# Tracksoar_v1.net
KiCad netlist of a schematic drawn in EAGLE
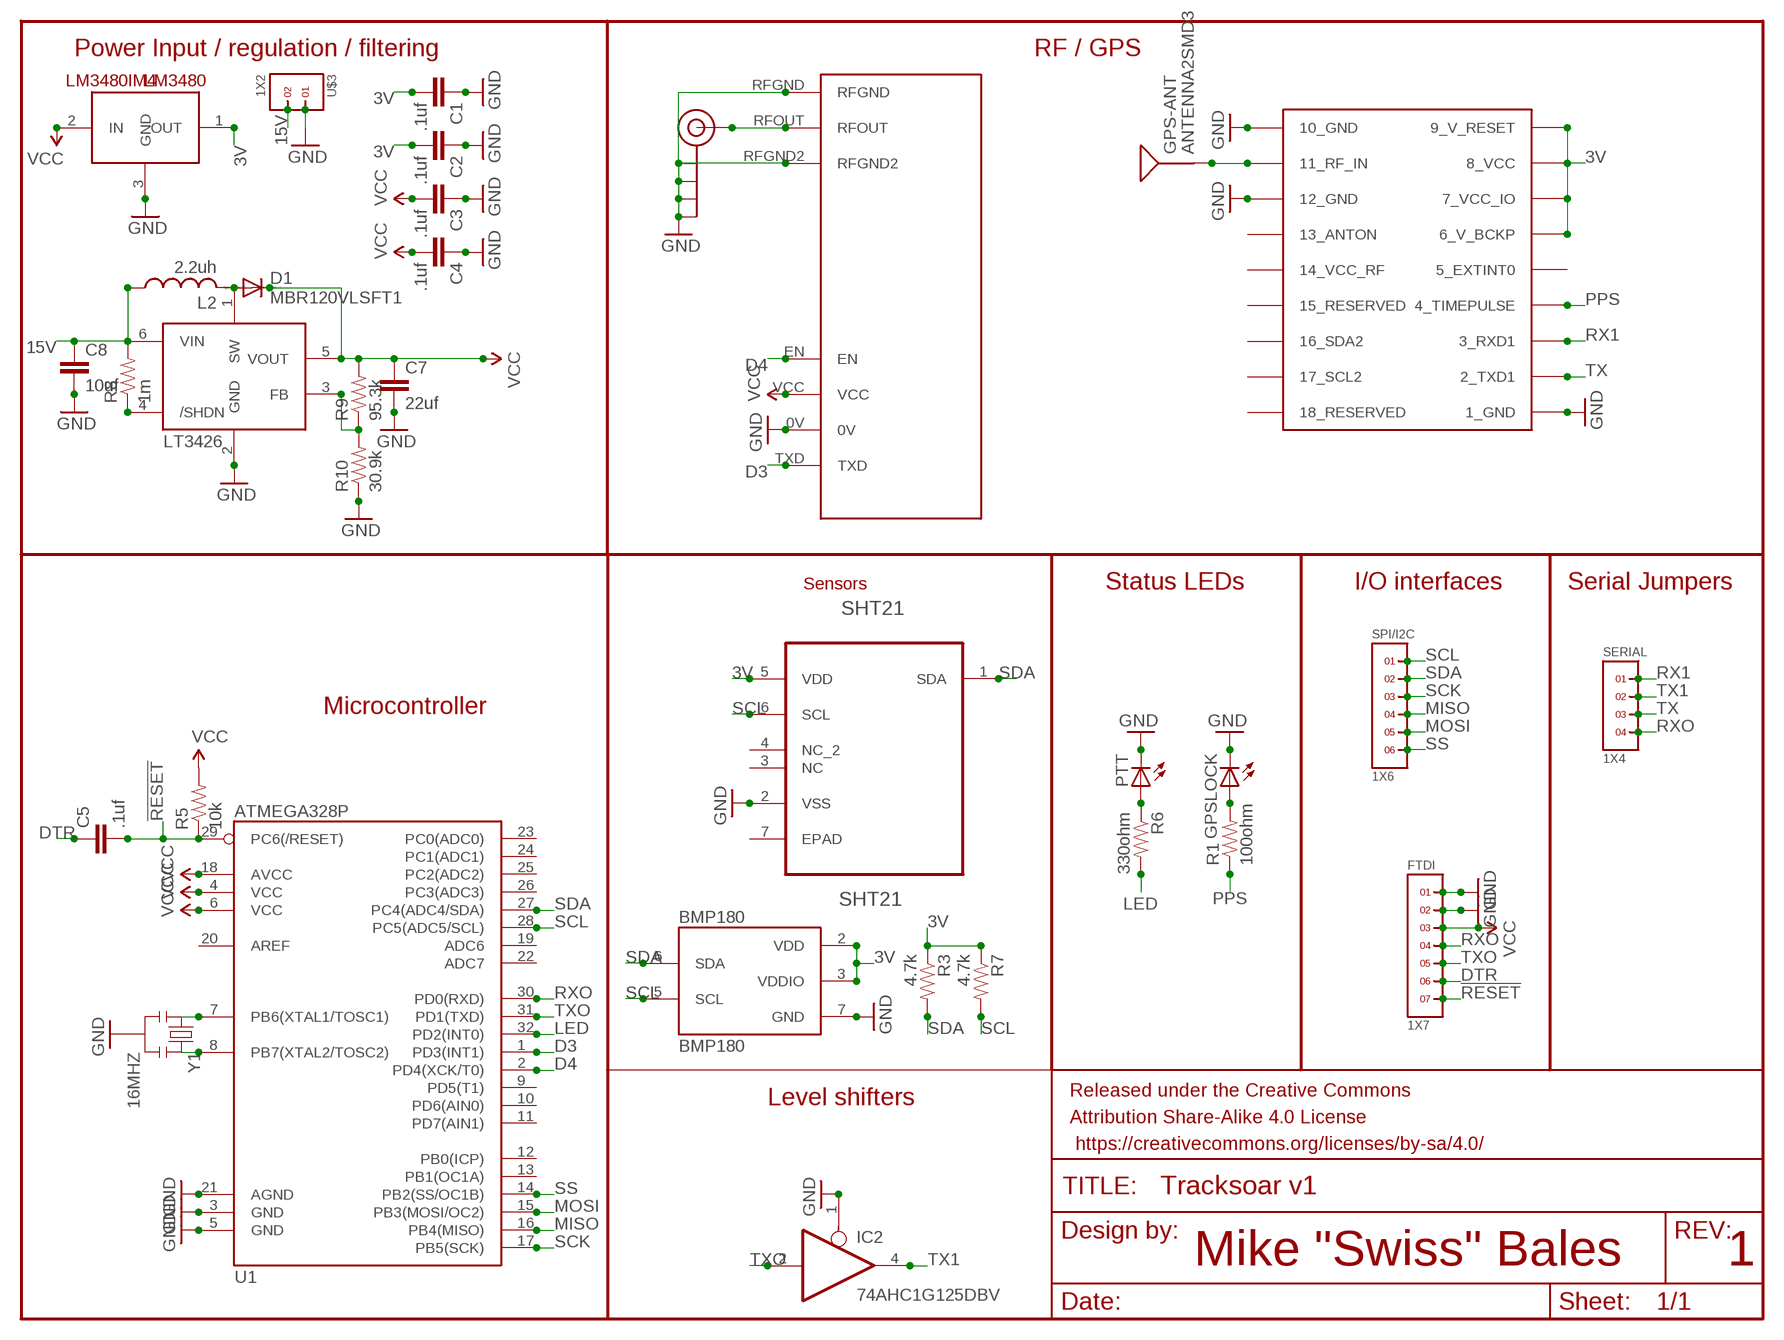
[diagram p0: schematic, sheet 1]

(export (version "E")
  (design (tool "Eeschema 10.0.6"))
  (components
    (comp (ref "BMP180")
      (value "BMP180")
      (footprint "eagle-import:BMP180")
      (libsource (lib "eagle-import") (part "BMP180"))
    )
    (comp (ref "C1")
      (value ".1uf")
      (footprint "eagle-import:0805")
      (libsource (lib "eagle-import") (part "CAP0805"))
    )
    (comp (ref "C2")
      (value ".1uf")
      (footprint "eagle-import:0805")
      (libsource (lib "eagle-import") (part "CAP0805"))
    )
    (comp (ref "C3")
      (value ".1uf")
      (footprint "eagle-import:0805")
      (libsource (lib "eagle-import") (part "CAP0805"))
    )
    (comp (ref "C4")
      (value ".1uf")
      (footprint "eagle-import:0805")
      (libsource (lib "eagle-import") (part "CAP0805"))
    )
    (comp (ref "C5")
      (value ".1uf")
      (footprint "eagle-import:0805")
      (libsource (lib "eagle-import") (part "CAP0805"))
    )
    (comp (ref "C7")
      (value "22uf")
      (footprint "eagle-import:0805")
      (libsource (lib "eagle-import") (part "CAP0805"))
    )
    (comp (ref "C8")
      (value "10uf")
      (footprint "eagle-import:0805")
      (libsource (lib "eagle-import") (part "CAP0805"))
    )
    (comp (ref "D1")
      (value "MBR120VLSFT1")
      (footprint "eagle-import:SOD123")
      (libsource (lib "eagle-import") (part "DIODE-SOD123"))
    )
    (comp (ref "FRAME1")
      (value "FRAME-LETTER")
      (footprint "eagle-import:CREATIVE_COMMONS")
      (libsource (lib "eagle-import") (part "FRAME-LETTER"))
    )
    (comp (ref "FTDI")
      (value "1X7")
      (footprint "eagle-import:1X7")
      (libsource (lib "eagle-import") (part "1X7"))
    )
    (comp (ref "GPS-ANT")
      (value "ANTENNA2SMD3")
      (footprint "eagle-import:ANTENNA-CHIP4")
      (libsource (lib "eagle-import") (part "ANTENNA2SMD3"))
    )
    (comp (ref "GPSLOCK")
      (value "LEDCHIP-LED0805")
      (footprint "eagle-import:CHIP-LED0805")
      (libsource (lib "eagle-import") (part "LEDCHIP-LED0805"))
    )
    (comp (ref "IC2")
      (value "74AHC1G125DBV")
      (footprint "eagle-import:SOT23-5")
      (libsource (lib "eagle-import") (part "741G125DBVAHC"))
    )
    (comp (ref "J$1")
      (value "SMA_EDGE")
      (footprint "eagle-import:SMA-EDGE")
      (libsource (lib "eagle-import") (part "SMA_EDGE"))
    )
    (comp (ref "L2")
      (value "2.2uh")
      (footprint "eagle-import:L1812")
      (libsource (lib "eagle-import") (part "L-USL1812"))
    )
    (comp (ref "LM3480")
      (value "LM3480IM4")
      (footprint "eagle-import:SOT23-3")
      (libsource (lib "eagle-import") (part "LM3480IM4"))
    )
    (comp (ref "LT3426")
      (value "LT3426")
      (footprint "eagle-import:SOT23-6")
      (libsource (lib "eagle-import") (part "LT3426"))
    )
    (comp (ref "PTT")
      (value "LEDCHIP-LED0805")
      (footprint "eagle-import:CHIP-LED0805")
      (libsource (lib "eagle-import") (part "LEDCHIP-LED0805"))
    )
    (comp (ref "R1")
      (value "100ohm")
      (footprint "eagle-import:0805")
      (libsource (lib "eagle-import") (part "RESISTOR0805-RES"))
    )
    (comp (ref "R3")
      (value "4.7k")
      (footprint "eagle-import:0805")
      (libsource (lib "eagle-import") (part "RESISTOR0805-RES"))
    )
    (comp (ref "R5")
      (value "10k")
      (footprint "eagle-import:0805")
      (libsource (lib "eagle-import") (part "RESISTOR0805-RES"))
    )
    (comp (ref "R6")
      (value "330ohm")
      (footprint "eagle-import:0805")
      (libsource (lib "eagle-import") (part "RESISTOR0805-RES"))
    )
    (comp (ref "R7")
      (value "4.7k")
      (footprint "eagle-import:0805")
      (libsource (lib "eagle-import") (part "RESISTOR0805-RES"))
    )
    (comp (ref "R8")
      (value "1m")
      (footprint "eagle-import:0805")
      (libsource (lib "eagle-import") (part "RESISTOR0805-RES"))
    )
    (comp (ref "R9")
      (value "95.3k")
      (footprint "eagle-import:0805")
      (libsource (lib "eagle-import") (part "RESISTOR0805-RES"))
    )
    (comp (ref "R10")
      (value "30.9k")
      (footprint "eagle-import:0805")
      (libsource (lib "eagle-import") (part "RESISTOR0805-RES"))
    )
    (comp (ref "SERIAL")
      (value "1X4")
      (footprint "eagle-import:1X4")
      (libsource (lib "eagle-import") (part "1X4"))
    )
    (comp (ref "SHT21")
      (value "SHT21")
      (footprint "eagle-import:DFN300X300X110-7N")
      (libsource (lib "eagle-import") (part "SHT21"))
    )
    (comp (ref "SPI/I2C")
      (value "1X6")
      (footprint "eagle-import:1X6")
      (libsource (lib "eagle-import") (part "1X6"))
    )
    (comp (ref "U$1")
      (value "UBLOX_MAX")
      (footprint "eagle-import:UBLOX_MAX")
      (libsource (lib "eagle-import") (part "UBLOX_MAX"))
    )
    (comp (ref "U$2")
      (value "RADIOMETRIX-HX1")
      (footprint "eagle-import:RADIOMETRIX-HX1")
      (libsource (lib "eagle-import") (part "RADIOMETRIX-HX1"))
    )
    (comp (ref "U$3")
      (value "1X2")
      (footprint "eagle-import:1X2")
      (libsource (lib "eagle-import") (part "1X2"))
    )
    (comp (ref "U1")
      (value "ATMEGA328P")
      (footprint "eagle-import:MLF32")
      (libsource (lib "eagle-import") (part "ATMEGA168MLF"))
    )
    (comp (ref "Y1")
      (value "16MHZ")
      (footprint "eagle-import:RESONATOR-SMD")
      (libsource (lib "eagle-import") (part "RESONATOR16MHZ"))
    )
  )
  (nets
    (net (code "1") (name "/3V") (class "Default")
      (node (ref "BMP180") (pin "2") (pinfunction "VDD_2") (pintype "power_in"))
      (node (ref "BMP180") (pin "3") (pinfunction "VDDIO_3") (pintype "power_in"))
      (node (ref "C1") (pin "2") (pinfunction "2_2") (pintype "passive"))
      (node (ref "C2") (pin "2") (pinfunction "2_2") (pintype "passive"))
      (node (ref "LM3480") (pin "1") (pinfunction "OUT_1") (pintype "bidirectional"))
      (node (ref "R3") (pin "1") (pinfunction "1_1") (pintype "passive"))
      (node (ref "R7") (pin "1") (pinfunction "1_1") (pintype "passive"))
      (node (ref "SHT21") (pin "5") (pinfunction "VDD_5") (pintype "power_in"))
      (node (ref "U$1") (pin "6_V_BCKP") (pinfunction "6_V_BCKP_6_V_BCKP") (pintype "bidirectional"))
      (node (ref "U$1") (pin "7_VCC_IO") (pinfunction "7_VCC_IO_7_VCC_IO") (pintype "power_in"))
      (node (ref "U$1") (pin "8_VCC") (pinfunction "8_VCC_8_VCC") (pintype "power_in"))
      (node (ref "U$1") (pin "9_V_RESET") (pinfunction "9_V_RESET_9_V_RESET") (pintype "power_in"))
    )
    (net (code "2") (name "/15V") (class "Default")
      (node (ref "C8") (pin "1") (pinfunction "1_1") (pintype "passive"))
      (node (ref "L2") (pin "1") (pinfunction "1_1") (pintype "passive"))
      (node (ref "LT3426") (pin "6") (pinfunction "VIN_6") (pintype "input"))
      (node (ref "R8") (pin "2") (pinfunction "2_2") (pintype "passive"))
      (node (ref "U$3") (pin "2") (pinfunction "2_2") (pintype "bidirectional"))
    )
    (net (code "3") (name "/D3") (class "Default")
      (node (ref "U$2") (pin "TXD") (pinfunction "TXD_TXD") (pintype "bidirectional"))
      (node (ref "U1") (pin "1") (pinfunction "PD3(INT1)_1") (pintype "bidirectional"))
    )
    (net (code "4") (name "/D4") (class "Default")
      (node (ref "U$2") (pin "EN") (pinfunction "EN_EN") (pintype "bidirectional"))
      (node (ref "U1") (pin "2") (pinfunction "PD4(XCK/T0)_2") (pintype "bidirectional"))
    )
    (net (code "5") (name "/DTR") (class "Default")
      (node (ref "C5") (pin "1") (pinfunction "1_1") (pintype "passive"))
      (node (ref "FTDI") (pin "6") (pinfunction "6_6") (pintype "bidirectional"))
    )
    (net (code "6") (name "/LED") (class "Default")
      (node (ref "R6") (pin "2") (pinfunction "2_2") (pintype "passive"))
      (node (ref "U1") (pin "32") (pinfunction "PD2(INT0)_32") (pintype "bidirectional"))
    )
    (net (code "7") (name "/MISO") (class "Default")
      (node (ref "SPI/I2C") (pin "4") (pinfunction "4_4") (pintype "bidirectional"))
      (node (ref "U1") (pin "16") (pinfunction "PB4(MISO)_16") (pintype "bidirectional"))
    )
    (net (code "8") (name "/MOSI") (class "Default")
      (node (ref "SPI/I2C") (pin "5") (pinfunction "5_5") (pintype "bidirectional"))
      (node (ref "U1") (pin "15") (pinfunction "PB3(MOSI/OC2)_15") (pintype "bidirectional"))
    )
    (net (code "9") (name "/PPS") (class "Default")
      (node (ref "R1") (pin "1") (pinfunction "1_1") (pintype "passive"))
      (node (ref "U$1") (pin "4_TIMEPULSE") (pinfunction "4_TIMEPULSE_4_TIMEPULSE") (pintype "bidirectional"))
    )
    (net (code "10") (name "/RX1") (class "Default")
      (node (ref "SERIAL") (pin "1") (pinfunction "1_1") (pintype "bidirectional"))
      (node (ref "U$1") (pin "3_RXD1") (pinfunction "3_RXD1_3_RXD1") (pintype "bidirectional"))
    )
    (net (code "11") (name "/RXO") (class "Default")
      (node (ref "FTDI") (pin "4") (pinfunction "4_4") (pintype "bidirectional"))
      (node (ref "SERIAL") (pin "4") (pinfunction "4_4") (pintype "bidirectional"))
      (node (ref "U1") (pin "30") (pinfunction "PD0(RXD)_30") (pintype "bidirectional"))
    )
    (net (code "12") (name "/SCK") (class "Default")
      (node (ref "SPI/I2C") (pin "3") (pinfunction "3_3") (pintype "bidirectional"))
      (node (ref "U1") (pin "17") (pinfunction "PB5(SCK)_17") (pintype "bidirectional"))
    )
    (net (code "13") (name "/SCL") (class "Default")
      (node (ref "BMP180") (pin "5") (pinfunction "SCL_5") (pintype "input"))
      (node (ref "R7") (pin "2") (pinfunction "2_2") (pintype "passive"))
      (node (ref "SHT21") (pin "6") (pinfunction "SCL_6") (pintype "input"))
      (node (ref "SPI/I2C") (pin "1") (pinfunction "1_1") (pintype "bidirectional"))
      (node (ref "U1") (pin "28") (pinfunction "PC5(ADC5/SCL)_28") (pintype "bidirectional"))
    )
    (net (code "14") (name "/SDA") (class "Default")
      (node (ref "BMP180") (pin "6") (pinfunction "SDA_6") (pintype "bidirectional"))
      (node (ref "R3") (pin "2") (pinfunction "2_2") (pintype "passive"))
      (node (ref "SHT21") (pin "1") (pinfunction "SDA_1") (pintype "bidirectional"))
      (node (ref "SPI/I2C") (pin "2") (pinfunction "2_2") (pintype "bidirectional"))
      (node (ref "U1") (pin "27") (pinfunction "PC4(ADC4/SDA)_27") (pintype "bidirectional"))
    )
    (net (code "15") (name "/SS") (class "Default")
      (node (ref "SPI/I2C") (pin "6") (pinfunction "6_6") (pintype "bidirectional"))
      (node (ref "U1") (pin "14") (pinfunction "PB2(SS/OC1B)_14") (pintype "bidirectional"))
    )
    (net (code "16") (name "/TX") (class "Default")
      (node (ref "SERIAL") (pin "3") (pinfunction "3_3") (pintype "bidirectional"))
      (node (ref "U$1") (pin "2_TXD1") (pinfunction "2_TXD1_2_TXD1") (pintype "bidirectional"))
    )
    (net (code "17") (name "/TX1") (class "Default")
      (node (ref "IC2") (pin "4") (pinfunction "O_4") (pintype "tri_state"))
      (node (ref "SERIAL") (pin "2") (pinfunction "2_2") (pintype "bidirectional"))
    )
    (net (code "18") (name "/TXO") (class "Default")
      (node (ref "FTDI") (pin "5") (pinfunction "5_5") (pintype "bidirectional"))
      (node (ref "IC2") (pin "2") (pinfunction "I_2") (pintype "input"))
      (node (ref "U1") (pin "31") (pinfunction "PD1(TXD)_31") (pintype "bidirectional"))
    )
    (net (code "19") (name "/~{RESET}") (class "Default")
      (node (ref "C5") (pin "2") (pinfunction "2_2") (pintype "passive"))
      (node (ref "FTDI") (pin "7") (pinfunction "7_7") (pintype "bidirectional"))
      (node (ref "R5") (pin "1") (pinfunction "1_1") (pintype "passive"))
      (node (ref "U1") (pin "29") (pinfunction "PC6(/RESET)_29") (pintype "bidirectional"))
    )
    (net (code "20") (name "GND") (class "Default")
      (node (ref "BMP180") (pin "7") (pinfunction "GND_7") (pintype "power_in"))
      (node (ref "C1") (pin "1") (pinfunction "1_1") (pintype "passive"))
      (node (ref "C2") (pin "1") (pinfunction "1_1") (pintype "passive"))
      (node (ref "C3") (pin "1") (pinfunction "1_1") (pintype "passive"))
      (node (ref "C4") (pin "1") (pinfunction "1_1") (pintype "passive"))
      (node (ref "C7") (pin "2") (pinfunction "2_2") (pintype "passive"))
      (node (ref "C8") (pin "2") (pinfunction "2_2") (pintype "passive"))
      (node (ref "FTDI") (pin "1") (pinfunction "1_1") (pintype "bidirectional"))
      (node (ref "FTDI") (pin "2") (pinfunction "2_2") (pintype "bidirectional"))
      (node (ref "GPSLOCK") (pin "C") (pinfunction "C_C") (pintype "passive"))
      (node (ref "IC2") (pin "1") (pinfunction "OE_1") (pintype "input"))
      (node (ref "J$1") (pin "GND@0") (pinfunction "GND_GND@0") (pintype "bidirectional"))
      (node (ref "J$1") (pin "GND@1") (pinfunction "GND_GND@1") (pintype "bidirectional"))
      (node (ref "J$1") (pin "GND@2") (pinfunction "GND_GND@2") (pintype "bidirectional"))
      (node (ref "J$1") (pin "GND@3") (pinfunction "GND_GND@3") (pintype "bidirectional"))
      (node (ref "LM3480") (pin "3") (pinfunction "GND_3") (pintype "bidirectional"))
      (node (ref "LT3426") (pin "2") (pinfunction "GND_2") (pintype "power_in"))
      (node (ref "PTT") (pin "C") (pinfunction "C_C") (pintype "passive"))
      (node (ref "R10") (pin "1") (pinfunction "1_1") (pintype "passive"))
      (node (ref "SHT21") (pin "2") (pinfunction "VSS_2") (pintype "power_in"))
      (node (ref "U$1") (pin "10_GND") (pinfunction "10_GND_10_GND") (pintype "power_in"))
      (node (ref "U$1") (pin "12_GND") (pinfunction "12_GND_12_GND") (pintype "power_in"))
      (node (ref "U$1") (pin "1_GND") (pinfunction "1_GND_1_GND") (pintype "power_in"))
      (node (ref "U$2") (pin "0V") (pinfunction "0V_0V") (pintype "bidirectional"))
      (node (ref "U$2") (pin "RFGND") (pinfunction "RFGND_RFGND") (pintype "bidirectional"))
      (node (ref "U$2") (pin "RFGND2") (pinfunction "RFGND2_RFGND2") (pintype "bidirectional"))
      (node (ref "U$3") (pin "1") (pinfunction "1_1") (pintype "bidirectional"))
      (node (ref "U1") (pin "21") (pinfunction "AGND_21") (pintype "bidirectional"))
      (node (ref "U1") (pin "3") (pinfunction "GND_3") (pintype "bidirectional"))
      (node (ref "U1") (pin "5") (pinfunction "GND_5") (pintype "bidirectional"))
      (node (ref "Y1") (pin "2") (pinfunction "2_2") (pintype "passive"))
    )
    (net (code "21") (name "Net-(GPS-ANT-SIGNAL)") (class "Default")
      (node (ref "GPS-ANT") (pin "SIG") (pinfunction "SIGNAL_SIG") (pintype "bidirectional"))
      (node (ref "U$1") (pin "11_RF_IN") (pinfunction "11_RF_IN_11_RF_IN") (pintype "bidirectional"))
    )
    (net (code "22") (name "Net-(GPSLOCK-PadA)") (class "Default")
      (node (ref "GPSLOCK") (pin "A") (pinfunction "A_A") (pintype "passive"))
      (node (ref "R1") (pin "2") (pinfunction "2_2") (pintype "passive"))
    )
    (net (code "23") (name "Net-(J$1-SIGNAL)") (class "Default")
      (node (ref "J$1") (pin "SIG") (pinfunction "SIGNAL_SIG") (pintype "bidirectional"))
      (node (ref "U$2") (pin "RFOUT") (pinfunction "RFOUT_RFOUT") (pintype "bidirectional"))
    )
    (net (code "24") (name "Net-(LT3426-FB)") (class "Default")
      (node (ref "LT3426") (pin "3") (pinfunction "FB_3") (pintype "input"))
      (node (ref "R10") (pin "2") (pinfunction "2_2") (pintype "passive"))
      (node (ref "R9") (pin "1") (pinfunction "1_1") (pintype "passive"))
    )
    (net (code "25") (name "Net-(LT3426-SW)") (class "Default")
      (node (ref "D1") (pin "A") (pinfunction "A_A") (pintype "passive"))
      (node (ref "L2") (pin "2") (pinfunction "2_2") (pintype "passive"))
      (node (ref "LT3426") (pin "1") (pinfunction "SW_1") (pintype "output"))
    )
    (net (code "26") (name "Net-(LT3426-{slash}SHDN)") (class "Default")
      (node (ref "LT3426") (pin "4") (pinfunction "/SHDN_4") (pintype "input"))
      (node (ref "R8") (pin "1") (pinfunction "1_1") (pintype "passive"))
    )
    (net (code "27") (name "Net-(PTT-PadA)") (class "Default")
      (node (ref "PTT") (pin "A") (pinfunction "A_A") (pintype "passive"))
      (node (ref "R6") (pin "1") (pinfunction "1_1") (pintype "passive"))
    )
    (net (code "28") (name "Net-(U1-PB6(XTAL1{slash}TOSC1))") (class "Default")
      (node (ref "U1") (pin "7") (pinfunction "PB6(XTAL1/TOSC1)_7") (pintype "bidirectional"))
      (node (ref "Y1") (pin "1") (pinfunction "1_1") (pintype "passive"))
    )
    (net (code "29") (name "Net-(U1-PB7(XTAL2{slash}TOSC2))") (class "Default")
      (node (ref "U1") (pin "8") (pinfunction "PB7(XTAL2/TOSC2)_8") (pintype "bidirectional"))
      (node (ref "Y1") (pin "3") (pinfunction "3_3") (pintype "passive"))
    )
    (net (code "30") (name "VCC") (class "Default")
      (node (ref "C3") (pin "2") (pinfunction "2_2") (pintype "passive"))
      (node (ref "C4") (pin "2") (pinfunction "2_2") (pintype "passive"))
      (node (ref "C7") (pin "1") (pinfunction "1_1") (pintype "passive"))
      (node (ref "D1") (pin "C") (pinfunction "C_C") (pintype "passive"))
      (node (ref "FTDI") (pin "3") (pinfunction "3_3") (pintype "bidirectional"))
      (node (ref "LM3480") (pin "2") (pinfunction "IN_2") (pintype "bidirectional"))
      (node (ref "LT3426") (pin "5") (pinfunction "VOUT_5") (pintype "output"))
      (node (ref "R5") (pin "2") (pinfunction "2_2") (pintype "passive"))
      (node (ref "R9") (pin "2") (pinfunction "2_2") (pintype "passive"))
      (node (ref "U$2") (pin "VCC") (pinfunction "VCC_VCC") (pintype "bidirectional"))
      (node (ref "U1") (pin "18") (pinfunction "AVCC_18") (pintype "bidirectional"))
      (node (ref "U1") (pin "4") (pinfunction "VCC_4") (pintype "bidirectional"))
      (node (ref "U1") (pin "6") (pinfunction "VCC_6") (pintype "bidirectional"))
    )
    (net (code "31") (name "unconnected-(SHT21-EPAD-Pad7)") (class "Default")
      (node (ref "SHT21") (pin "7") (pinfunction "EPAD_7") (pintype "passive"))
    )
    (net (code "32") (name "unconnected-(SHT21-NC-Pad3)") (class "Default")
      (node (ref "SHT21") (pin "3") (pinfunction "NC_3") (pintype "no_connect"))
    )
    (net (code "33") (name "unconnected-(SHT21-NC_2-Pad4)") (class "Default")
      (node (ref "SHT21") (pin "4") (pinfunction "NC_2_4") (pintype "no_connect"))
    )
    (net (code "34") (name "unconnected-(U$1-Pad5_EXTINT0)") (class "Default")
      (node (ref "U$1") (pin "5_EXTINT0") (pinfunction "5_EXTINT0_5_EXTINT0") (pintype "bidirectional"))
    )
    (net (code "35") (name "unconnected-(U$1-Pad13_ANTON)") (class "Default")
      (node (ref "U$1") (pin "13_ANTON") (pinfunction "13_ANTON_13_ANTON") (pintype "bidirectional"))
    )
    (net (code "36") (name "unconnected-(U$1-Pad14_VCC_RF)") (class "Default")
      (node (ref "U$1") (pin "14_VCC_RF") (pinfunction "14_VCC_RF_14_VCC_RF") (pintype "bidirectional"))
    )
    (net (code "37") (name "unconnected-(U$1-Pad15_RESERVED)") (class "Default")
      (node (ref "U$1") (pin "15_RESERVED") (pinfunction "15_RESERVED_15_RESERVED") (pintype "bidirectional"))
    )
    (net (code "38") (name "unconnected-(U$1-Pad16_SDA2)") (class "Default")
      (node (ref "U$1") (pin "16_SDA2") (pinfunction "16_SDA2_16_SDA2") (pintype "bidirectional"))
    )
    (net (code "39") (name "unconnected-(U$1-Pad17_SCL2)") (class "Default")
      (node (ref "U$1") (pin "17_SCL2") (pinfunction "17_SCL2_17_SCL2") (pintype "bidirectional"))
    )
    (net (code "40") (name "unconnected-(U$1-Pad18_RESERVED)") (class "Default")
      (node (ref "U$1") (pin "18_RESERVED") (pinfunction "18_RESERVED_18_RESERVED") (pintype "bidirectional"))
    )
    (net (code "41") (name "unconnected-(U1-ADC6-Pad19)") (class "Default")
      (node (ref "U1") (pin "19") (pinfunction "ADC6_19") (pintype "bidirectional"))
    )
    (net (code "42") (name "unconnected-(U1-ADC7-Pad22)") (class "Default")
      (node (ref "U1") (pin "22") (pinfunction "ADC7_22") (pintype "bidirectional"))
    )
    (net (code "43") (name "unconnected-(U1-AREF-Pad20)") (class "Default")
      (node (ref "U1") (pin "20") (pinfunction "AREF_20") (pintype "bidirectional"))
    )
    (net (code "44") (name "unconnected-(U1-PB0(ICP)-Pad12)") (class "Default")
      (node (ref "U1") (pin "12") (pinfunction "PB0(ICP)_12") (pintype "bidirectional"))
    )
    (net (code "45") (name "unconnected-(U1-PB1(OC1A)-Pad13)") (class "Default")
      (node (ref "U1") (pin "13") (pinfunction "PB1(OC1A)_13") (pintype "bidirectional"))
    )
    (net (code "46") (name "unconnected-(U1-PC0(ADC0)-Pad23)") (class "Default")
      (node (ref "U1") (pin "23") (pinfunction "PC0(ADC0)_23") (pintype "bidirectional"))
    )
    (net (code "47") (name "unconnected-(U1-PC1(ADC1)-Pad24)") (class "Default")
      (node (ref "U1") (pin "24") (pinfunction "PC1(ADC1)_24") (pintype "bidirectional"))
    )
    (net (code "48") (name "unconnected-(U1-PC2(ADC2)-Pad25)") (class "Default")
      (node (ref "U1") (pin "25") (pinfunction "PC2(ADC2)_25") (pintype "bidirectional"))
    )
    (net (code "49") (name "unconnected-(U1-PC3(ADC3)-Pad26)") (class "Default")
      (node (ref "U1") (pin "26") (pinfunction "PC3(ADC3)_26") (pintype "bidirectional"))
    )
    (net (code "50") (name "unconnected-(U1-PD5(T1)-Pad9)") (class "Default")
      (node (ref "U1") (pin "9") (pinfunction "PD5(T1)_9") (pintype "bidirectional"))
    )
    (net (code "51") (name "unconnected-(U1-PD6(AIN0)-Pad10)") (class "Default")
      (node (ref "U1") (pin "10") (pinfunction "PD6(AIN0)_10") (pintype "bidirectional"))
    )
    (net (code "52") (name "unconnected-(U1-PD7(AIN1)-Pad11)") (class "Default")
      (node (ref "U1") (pin "11") (pinfunction "PD7(AIN1)_11") (pintype "bidirectional"))
    )
  )
)
